# MotorBoardSch.net
KiCad netlist of a schematic drawn in Altium Designer
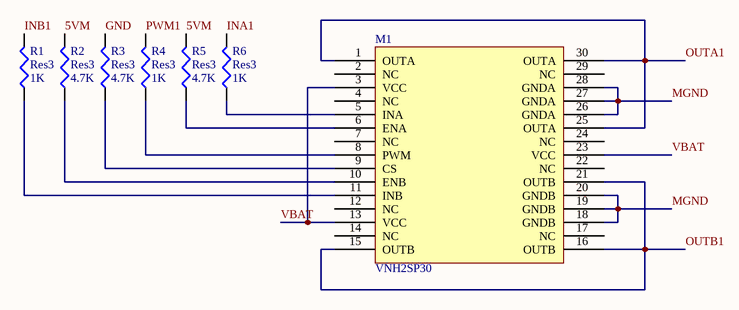
[diagram p0: MotorBoardSch.SchDoc]

(export (version "E")
  (design (tool "Eeschema 10.0.6"))
  (components
    (comp (ref "M1") (value "VNH2SP30") (footprint "VNH5019") (libsource (lib "USST2016") (part "VNH2SP30")))
    (comp (ref "R1")
      (value "Res3")
      (footprint "12Z-2010")
      (description "Resistor")
      (fields (field (name "ALTIUM_VALUE") "1K") (field (name "PUBLISHER") "Altium Limited"))
      (libsource (lib "Miscellaneous Devices") (part "Res3"))
    )
    (comp (ref "R2")
      (value "Res3")
      (footprint "12Z-2010")
      (description "Resistor")
      (fields (field (name "ALTIUM_VALUE") "4.7K") (field (name "PUBLISHER") "Altium Limited"))
      (libsource (lib "Miscellaneous Devices") (part "Res3"))
    )
    (comp (ref "R3")
      (value "Res3")
      (footprint "12Z-2010")
      (description "Resistor")
      (fields (field (name "ALTIUM_VALUE") "4.7K") (field (name "PUBLISHER") "Altium Limited"))
      (libsource (lib "Miscellaneous Devices") (part "Res3"))
    )
    (comp (ref "R4")
      (value "Res3")
      (footprint "12Z-2010")
      (description "Resistor")
      (fields (field (name "ALTIUM_VALUE") "1K") (field (name "PUBLISHER") "Altium Limited"))
      (libsource (lib "Miscellaneous Devices") (part "Res3"))
    )
    (comp (ref "R5")
      (value "Res3")
      (footprint "12Z-2010")
      (description "Resistor")
      (fields (field (name "ALTIUM_VALUE") "4.7K") (field (name "PUBLISHER") "Altium Limited"))
      (libsource (lib "Miscellaneous Devices") (part "Res3"))
    )
    (comp (ref "R6")
      (value "Res3")
      (footprint "12Z-2010")
      (description "Resistor")
      (fields (field (name "ALTIUM_VALUE") "1K") (field (name "PUBLISHER") "Altium Limited"))
      (libsource (lib "Miscellaneous Devices") (part "Res3"))
    )
  )
  (nets
    (net (code "1") (name "/5VM") (class "Default")
      (node (ref "R2") (pin "2") (pinfunction "2_2") (pintype "passive"))
      (node (ref "R5") (pin "2") (pinfunction "2_2") (pintype "passive"))
    )
    (net (code "2") (name "/GND") (class "Default")
      (node (ref "R3") (pin "2") (pinfunction "2_2") (pintype "passive"))
    )
    (net (code "3") (name "/INA1") (class "Default")
      (node (ref "R6") (pin "2") (pinfunction "2_2") (pintype "passive"))
    )
    (net (code "4") (name "/INB1") (class "Default")
      (node (ref "R1") (pin "2") (pinfunction "2_2") (pintype "passive"))
    )
    (net (code "5") (name "/MGND") (class "Default")
      (node (ref "M1") (pin "18") (pinfunction "GNDB_18") (pintype "passive"))
      (node (ref "M1") (pin "19") (pinfunction "GNDB_19") (pintype "passive"))
      (node (ref "M1") (pin "20") (pinfunction "GNDB_20") (pintype "passive"))
      (node (ref "M1") (pin "26") (pinfunction "GNDA_26") (pintype "passive"))
      (node (ref "M1") (pin "27") (pinfunction "GNDA_27") (pintype "passive"))
      (node (ref "M1") (pin "28") (pinfunction "GNDA_28") (pintype "passive"))
    )
    (net (code "6") (name "/OUTA1") (class "Default")
      (node (ref "M1") (pin "1") (pinfunction "OUTA_1") (pintype "passive"))
      (node (ref "M1") (pin "25") (pinfunction "OUTA_25") (pintype "passive"))
      (node (ref "M1") (pin "30") (pinfunction "OUTA_30") (pintype "passive"))
    )
    (net (code "7") (name "/OUTB1") (class "Default")
      (node (ref "M1") (pin "15") (pinfunction "OUTB_15") (pintype "passive"))
      (node (ref "M1") (pin "16") (pinfunction "OUTB_16") (pintype "passive"))
      (node (ref "M1") (pin "21") (pinfunction "OUTB_21") (pintype "passive"))
    )
    (net (code "8") (name "/PWM1") (class "Default")
      (node (ref "R4") (pin "2") (pinfunction "2_2") (pintype "passive"))
    )
    (net (code "9") (name "/VBAT") (class "Default")
      (node (ref "M1") (pin "13") (pinfunction "VCC_13") (pintype "passive"))
      (node (ref "M1") (pin "23") (pinfunction "VCC_23") (pintype "passive"))
      (node (ref "M1") (pin "3") (pinfunction "VCC_3") (pintype "passive"))
    )
    (net (code "10") (name "Net-(M1-CS)") (class "Default")
      (node (ref "M1") (pin "9") (pinfunction "CS_9") (pintype "passive"))
      (node (ref "R3") (pin "1") (pinfunction "1_1") (pintype "passive"))
    )
    (net (code "11") (name "Net-(M1-ENA)") (class "Default")
      (node (ref "M1") (pin "6") (pinfunction "ENA_6") (pintype "passive"))
      (node (ref "R5") (pin "1") (pinfunction "1_1") (pintype "passive"))
    )
    (net (code "12") (name "Net-(M1-ENB)") (class "Default")
      (node (ref "M1") (pin "10") (pinfunction "ENB_10") (pintype "passive"))
      (node (ref "R2") (pin "1") (pinfunction "1_1") (pintype "passive"))
    )
    (net (code "13") (name "Net-(M1-INA)") (class "Default")
      (node (ref "M1") (pin "5") (pinfunction "INA_5") (pintype "passive"))
      (node (ref "R6") (pin "1") (pinfunction "1_1") (pintype "passive"))
    )
    (net (code "14") (name "Net-(M1-INB)") (class "Default")
      (node (ref "M1") (pin "11") (pinfunction "INB_11") (pintype "passive"))
      (node (ref "R1") (pin "1") (pinfunction "1_1") (pintype "passive"))
    )
    (net (code "15") (name "Net-(M1-PWM)") (class "Default")
      (node (ref "M1") (pin "8") (pinfunction "PWM_8") (pintype "passive"))
      (node (ref "R4") (pin "1") (pinfunction "1_1") (pintype "passive"))
    )
    (net (code "16") (name "unconnected-(M1-NC-Pad2)") (class "Default")
      (node (ref "M1") (pin "2") (pinfunction "NC_2") (pintype "passive"))
    )
    (net (code "17") (name "unconnected-(M1-NC-Pad4)") (class "Default")
      (node (ref "M1") (pin "4") (pinfunction "NC_4") (pintype "passive"))
    )
    (net (code "18") (name "unconnected-(M1-NC-Pad7)") (class "Default")
      (node (ref "M1") (pin "7") (pinfunction "NC_7") (pintype "passive"))
    )
    (net (code "19") (name "unconnected-(M1-NC-Pad12)") (class "Default")
      (node (ref "M1") (pin "12") (pinfunction "NC_12") (pintype "passive"))
    )
    (net (code "20") (name "unconnected-(M1-NC-Pad14)") (class "Default")
      (node (ref "M1") (pin "14") (pinfunction "NC_14") (pintype "passive"))
    )
    (net (code "21") (name "unconnected-(M1-NC-Pad17)") (class "Default")
      (node (ref "M1") (pin "17") (pinfunction "NC_17") (pintype "passive"))
    )
    (net (code "22") (name "unconnected-(M1-NC-Pad22)") (class "Default")
      (node (ref "M1") (pin "22") (pinfunction "NC_22") (pintype "passive"))
    )
    (net (code "23") (name "unconnected-(M1-NC-Pad24)") (class "Default")
      (node (ref "M1") (pin "24") (pinfunction "NC_24") (pintype "passive"))
    )
    (net (code "24") (name "unconnected-(M1-NC-Pad29)") (class "Default")
      (node (ref "M1") (pin "29") (pinfunction "NC_29") (pintype "passive"))
    )
  )
)
